# snare_host_brd.net
KiCad netlist of a schematic drawn in EAGLE
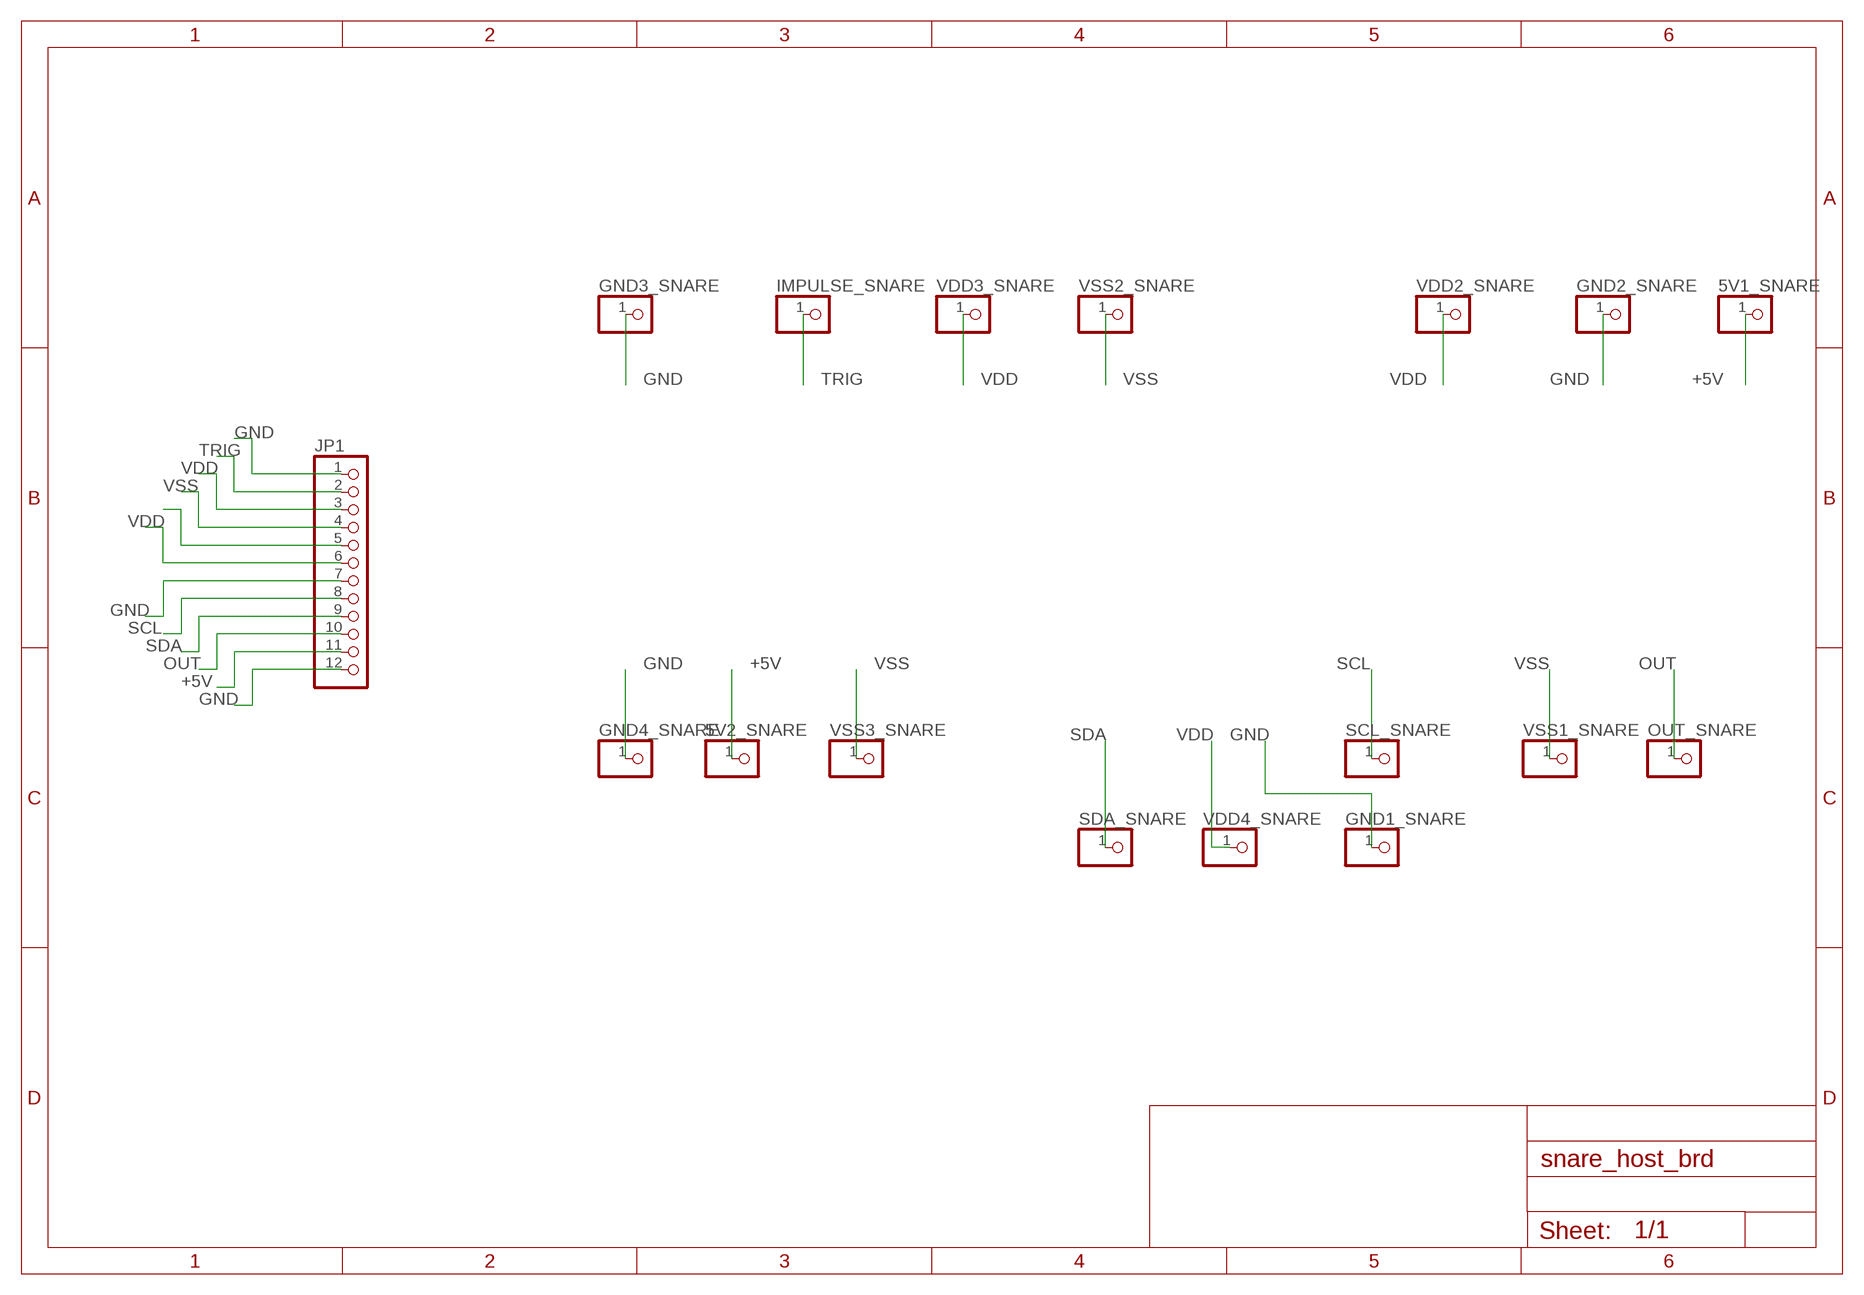
[diagram p0: schematic, sheet 1]

(export (version "E")
  (design (tool "Eeschema 10.0.6"))
  (components
    (comp (ref "5V1_SNARE")
      (value "PINHD-1X1")
      (footprint "eagle-import:1X01")
      (libsource (lib "eagle-import") (part "PINHD-1X1"))
    )
    (comp (ref "5V2_SNARE")
      (value "PINHD-1X1")
      (footprint "eagle-import:1X01")
      (libsource (lib "eagle-import") (part "PINHD-1X1"))
    )
    (comp (ref "GND1_SNARE")
      (value "PINHD-1X1")
      (footprint "eagle-import:1X01")
      (libsource (lib "eagle-import") (part "PINHD-1X1"))
    )
    (comp (ref "GND2_SNARE")
      (value "PINHD-1X1")
      (footprint "eagle-import:1X01")
      (libsource (lib "eagle-import") (part "PINHD-1X1"))
    )
    (comp (ref "GND3_SNARE")
      (value "PINHD-1X1")
      (footprint "eagle-import:1X01")
      (libsource (lib "eagle-import") (part "PINHD-1X1"))
    )
    (comp (ref "GND4_SNARE")
      (value "PINHD-1X1")
      (footprint "eagle-import:1X01")
      (libsource (lib "eagle-import") (part "PINHD-1X1"))
    )
    (comp (ref "IMPULSE_SNARE")
      (value "PINHD-1X1")
      (footprint "eagle-import:1X01")
      (libsource (lib "eagle-import") (part "PINHD-1X1"))
    )
    (comp (ref "JP1")
      (value "PINHD-1X12/90")
      (footprint "eagle-import:1X12_90")
      (libsource (lib "eagle-import") (part "PINHD-1X12/90"))
    )
    (comp (ref "OUT_SNARE")
      (value "PINHD-1X1")
      (footprint "eagle-import:1X01")
      (libsource (lib "eagle-import") (part "PINHD-1X1"))
    )
    (comp (ref "SCL_SNARE")
      (value "PINHD-1X1")
      (footprint "eagle-import:1X01")
      (libsource (lib "eagle-import") (part "PINHD-1X1"))
    )
    (comp (ref "SDA_SNARE")
      (value "PINHD-1X1")
      (footprint "eagle-import:1X01")
      (libsource (lib "eagle-import") (part "PINHD-1X1"))
    )
    (comp (ref "VDD2_SNARE")
      (value "PINHD-1X1")
      (footprint "eagle-import:1X01")
      (libsource (lib "eagle-import") (part "PINHD-1X1"))
    )
    (comp (ref "VDD3_SNARE")
      (value "PINHD-1X1")
      (footprint "eagle-import:1X01")
      (libsource (lib "eagle-import") (part "PINHD-1X1"))
    )
    (comp (ref "VDD4_SNARE")
      (value "PINHD-1X1")
      (footprint "eagle-import:1X01")
      (libsource (lib "eagle-import") (part "PINHD-1X1"))
    )
    (comp (ref "VSS1_SNARE")
      (value "PINHD-1X1")
      (footprint "eagle-import:1X01")
      (libsource (lib "eagle-import") (part "PINHD-1X1"))
    )
    (comp (ref "VSS2_SNARE")
      (value "PINHD-1X1")
      (footprint "eagle-import:1X01")
      (libsource (lib "eagle-import") (part "PINHD-1X1"))
    )
    (comp (ref "VSS3_SNARE")
      (value "PINHD-1X1")
      (footprint "eagle-import:1X01")
      (libsource (lib "eagle-import") (part "PINHD-1X1"))
    )
  )
  (nets
    (net (code "1") (name "/+5V") (class "Default")
      (node (ref "5V1_SNARE") (pin "1") (pinfunction "1_1") (pintype "passive"))
      (node (ref "5V2_SNARE") (pin "1") (pinfunction "1_1") (pintype "passive"))
      (node (ref "JP1") (pin "11") (pinfunction "11_11") (pintype "passive"))
    )
    (net (code "2") (name "/GND") (class "Default")
      (node (ref "GND1_SNARE") (pin "1") (pinfunction "1_1") (pintype "passive"))
      (node (ref "GND2_SNARE") (pin "1") (pinfunction "1_1") (pintype "passive"))
      (node (ref "GND3_SNARE") (pin "1") (pinfunction "1_1") (pintype "passive"))
      (node (ref "GND4_SNARE") (pin "1") (pinfunction "1_1") (pintype "passive"))
      (node (ref "JP1") (pin "1") (pinfunction "1_1") (pintype "passive"))
      (node (ref "JP1") (pin "12") (pinfunction "12_12") (pintype "passive"))
      (node (ref "JP1") (pin "7") (pinfunction "7_7") (pintype "passive"))
    )
    (net (code "3") (name "/OUT") (class "Default")
      (node (ref "JP1") (pin "10") (pinfunction "10_10") (pintype "passive"))
      (node (ref "OUT_SNARE") (pin "1") (pinfunction "1_1") (pintype "passive"))
    )
    (net (code "4") (name "/SCL") (class "Default")
      (node (ref "JP1") (pin "8") (pinfunction "8_8") (pintype "passive"))
      (node (ref "SCL_SNARE") (pin "1") (pinfunction "1_1") (pintype "passive"))
    )
    (net (code "5") (name "/SDA") (class "Default")
      (node (ref "JP1") (pin "9") (pinfunction "9_9") (pintype "passive"))
      (node (ref "SDA_SNARE") (pin "1") (pinfunction "1_1") (pintype "passive"))
    )
    (net (code "6") (name "/TRIG") (class "Default")
      (node (ref "IMPULSE_SNARE") (pin "1") (pinfunction "1_1") (pintype "passive"))
      (node (ref "JP1") (pin "2") (pinfunction "2_2") (pintype "passive"))
    )
    (net (code "7") (name "/VDD") (class "Default")
      (node (ref "JP1") (pin "3") (pinfunction "3_3") (pintype "passive"))
      (node (ref "JP1") (pin "6") (pinfunction "6_6") (pintype "passive"))
      (node (ref "VDD2_SNARE") (pin "1") (pinfunction "1_1") (pintype "passive"))
      (node (ref "VDD3_SNARE") (pin "1") (pinfunction "1_1") (pintype "passive"))
      (node (ref "VDD4_SNARE") (pin "1") (pinfunction "1_1") (pintype "passive"))
    )
    (net (code "8") (name "/VSS") (class "Default")
      (node (ref "JP1") (pin "4") (pinfunction "4_4") (pintype "passive"))
      (node (ref "VSS1_SNARE") (pin "1") (pinfunction "1_1") (pintype "passive"))
      (node (ref "VSS2_SNARE") (pin "1") (pinfunction "1_1") (pintype "passive"))
      (node (ref "VSS3_SNARE") (pin "1") (pinfunction "1_1") (pintype "passive"))
    )
    (net (code "9") (name "unconnected-(JP1-Pad5)") (class "Default")
      (node (ref "JP1") (pin "5") (pinfunction "5_5") (pintype "passive"))
    )
  )
)
